# Max2_FP_v2.net
KiCad netlist of a schematic drawn in EAGLE
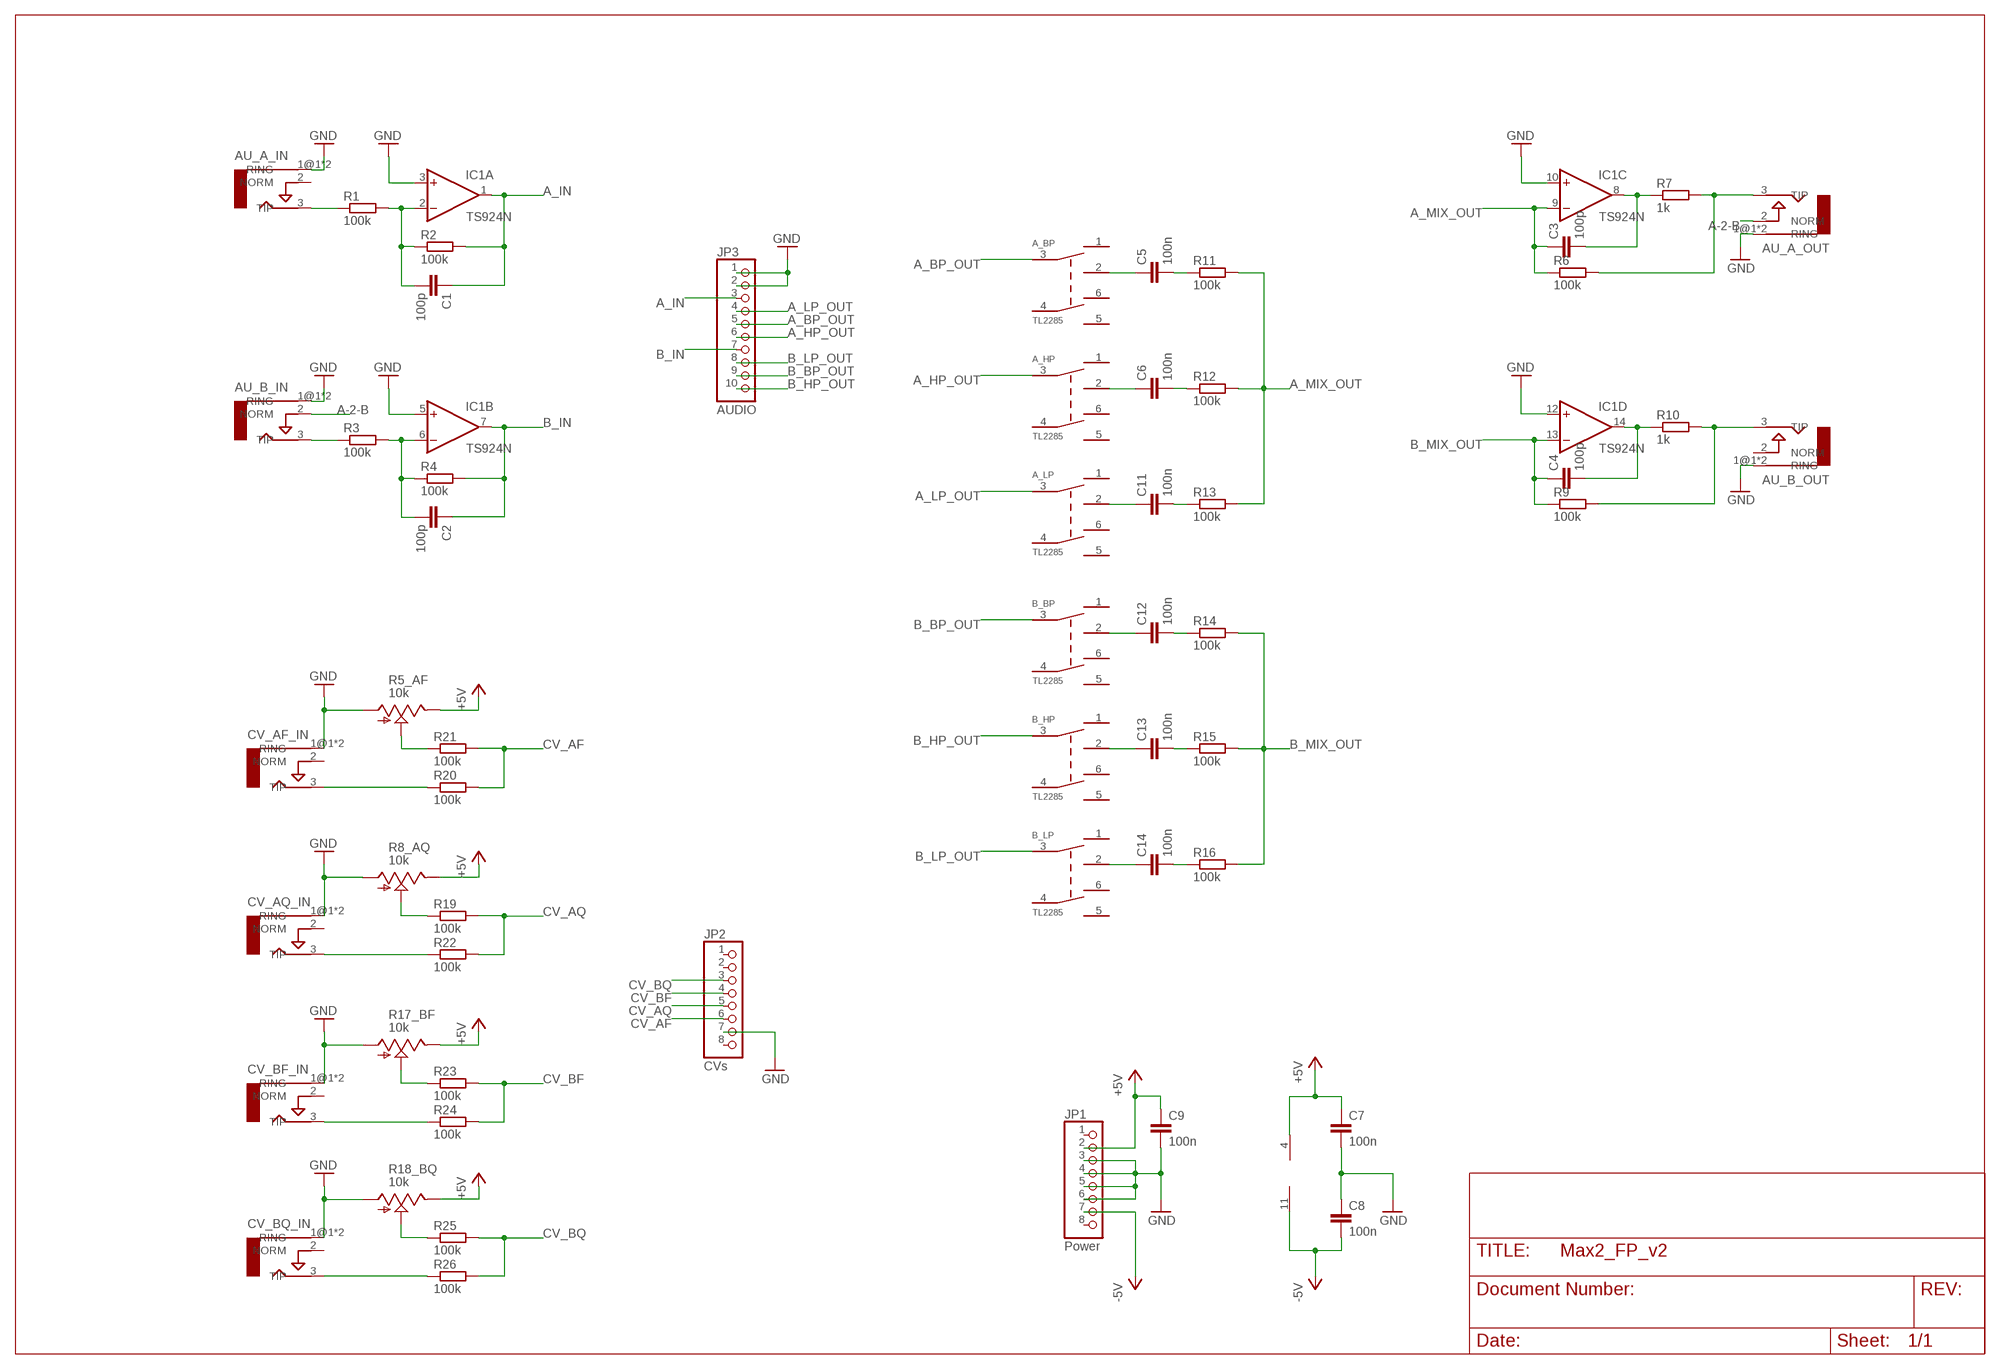
[diagram p0: schematic, sheet 1]

(export (version "E")
  (design (tool "Eeschema 10.0.6"))
  (components
    (comp (ref "AU_A_IN")
      (value "AUDIO-JACKERTHENVAR")
      (footprint "eagle-import:ERTHENVAR-JACK")
      (libsource (lib "eagle-import") (part "AUDIO-JACKERTHENVAR"))
    )
    (comp (ref "AU_A_OUT")
      (value "AUDIO-JACKERTHENVAR")
      (footprint "eagle-import:ERTHENVAR-JACK")
      (libsource (lib "eagle-import") (part "AUDIO-JACKERTHENVAR"))
    )
    (comp (ref "AU_B_IN")
      (value "AUDIO-JACKERTHENVAR")
      (footprint "eagle-import:ERTHENVAR-JACK")
      (libsource (lib "eagle-import") (part "AUDIO-JACKERTHENVAR"))
    )
    (comp (ref "AU_B_OUT")
      (value "AUDIO-JACKERTHENVAR")
      (footprint "eagle-import:ERTHENVAR-JACK")
      (libsource (lib "eagle-import") (part "AUDIO-JACKERTHENVAR"))
    )
    (comp (ref "A_BP")
      (value "TL2285")
      (footprint "eagle-import:TL2285_PCB")
      (libsource (lib "eagle-import") (part "TL2285"))
    )
    (comp (ref "A_HP")
      (value "TL2285")
      (footprint "eagle-import:TL2285_PCB")
      (libsource (lib "eagle-import") (part "TL2285"))
    )
    (comp (ref "A_LP")
      (value "TL2285")
      (footprint "eagle-import:TL2285_PCB")
      (libsource (lib "eagle-import") (part "TL2285"))
    )
    (comp (ref "B_BP")
      (value "TL2285")
      (footprint "eagle-import:TL2285_PCB")
      (libsource (lib "eagle-import") (part "TL2285"))
    )
    (comp (ref "B_HP")
      (value "TL2285")
      (footprint "eagle-import:TL2285_PCB")
      (libsource (lib "eagle-import") (part "TL2285"))
    )
    (comp (ref "B_LP")
      (value "TL2285")
      (footprint "eagle-import:TL2285_PCB")
      (libsource (lib "eagle-import") (part "TL2285"))
    )
    (comp (ref "C1")
      (value "100p")
      (footprint "eagle-import:C025-025X050")
      (libsource (lib "eagle-import") (part "C-EU025-025X050"))
    )
    (comp (ref "C2")
      (value "100p")
      (footprint "eagle-import:C025-025X050")
      (libsource (lib "eagle-import") (part "C-EU025-025X050"))
    )
    (comp (ref "C3")
      (value "100p")
      (footprint "eagle-import:C025-025X050")
      (libsource (lib "eagle-import") (part "C-EU025-025X050"))
    )
    (comp (ref "C4")
      (value "100p")
      (footprint "eagle-import:C025-025X050")
      (libsource (lib "eagle-import") (part "C-EU025-025X050"))
    )
    (comp (ref "C5")
      (value "100n")
      (footprint "eagle-import:C050-025X075")
      (libsource (lib "eagle-import") (part "C-EU050-025X075"))
    )
    (comp (ref "C6")
      (value "100n")
      (footprint "eagle-import:C050-025X075")
      (libsource (lib "eagle-import") (part "C-EU050-025X075"))
    )
    (comp (ref "C7")
      (value "100n")
      (footprint "eagle-import:C025-025X050")
      (libsource (lib "eagle-import") (part "C-EU025-025X050"))
    )
    (comp (ref "C8")
      (value "100n")
      (footprint "eagle-import:C025-025X050")
      (libsource (lib "eagle-import") (part "C-EU025-025X050"))
    )
    (comp (ref "C9")
      (value "100n")
      (footprint "eagle-import:C025-025X050")
      (libsource (lib "eagle-import") (part "C-EU025-025X050"))
    )
    (comp (ref "C11")
      (value "100n")
      (footprint "eagle-import:C050-025X075")
      (libsource (lib "eagle-import") (part "C-EU050-025X075"))
    )
    (comp (ref "C12")
      (value "100n")
      (footprint "eagle-import:C050-025X075")
      (libsource (lib "eagle-import") (part "C-EU050-025X075"))
    )
    (comp (ref "C13")
      (value "100n")
      (footprint "eagle-import:C050-025X075")
      (libsource (lib "eagle-import") (part "C-EU050-025X075"))
    )
    (comp (ref "C14")
      (value "100n")
      (footprint "eagle-import:C050-025X075")
      (libsource (lib "eagle-import") (part "C-EU050-025X075"))
    )
    (comp (ref "CV_AF_IN")
      (value "AUDIO-JACKERTHENVAR")
      (footprint "eagle-import:ERTHENVAR-JACK")
      (libsource (lib "eagle-import") (part "AUDIO-JACKERTHENVAR"))
    )
    (comp (ref "CV_AQ_IN")
      (value "AUDIO-JACKERTHENVAR")
      (footprint "eagle-import:ERTHENVAR-JACK")
      (libsource (lib "eagle-import") (part "AUDIO-JACKERTHENVAR"))
    )
    (comp (ref "CV_BF_IN")
      (value "AUDIO-JACKERTHENVAR")
      (footprint "eagle-import:ERTHENVAR-JACK")
      (libsource (lib "eagle-import") (part "AUDIO-JACKERTHENVAR"))
    )
    (comp (ref "CV_BQ_IN")
      (value "AUDIO-JACKERTHENVAR")
      (footprint "eagle-import:ERTHENVAR-JACK")
      (libsource (lib "eagle-import") (part "AUDIO-JACKERTHENVAR"))
    )
    (comp (ref "IC1")
      (value "TS924N")
      (footprint "eagle-import:DIL14")
      (libsource (lib "eagle-import") (part "TS924N"))
    )
    (comp (ref "JP1")
      (value "Power")
      (footprint "eagle-import:1X08")
      (libsource (lib "eagle-import") (part "PINHD-1X8"))
    )
    (comp (ref "JP2")
      (value "CVs")
      (footprint "eagle-import:1X08")
      (libsource (lib "eagle-import") (part "PINHD-1X8"))
    )
    (comp (ref "JP3")
      (value "AUDIO")
      (footprint "eagle-import:1X10")
      (libsource (lib "eagle-import") (part "PINHD-1X10"))
    )
    (comp (ref "R1")
      (value "100k")
      (footprint "eagle-import:0207_2V")
      (libsource (lib "eagle-import") (part "R-EU_0207/2V"))
    )
    (comp (ref "R2")
      (value "100k")
      (footprint "eagle-import:0207_2V")
      (libsource (lib "eagle-import") (part "R-EU_0207/2V"))
    )
    (comp (ref "R3")
      (value "100k")
      (footprint "eagle-import:0207_2V")
      (libsource (lib "eagle-import") (part "R-EU_0207/2V"))
    )
    (comp (ref "R4")
      (value "100k")
      (footprint "eagle-import:0207_2V")
      (libsource (lib "eagle-import") (part "R-EU_0207/2V"))
    )
    (comp (ref "R5_AF")
      (value "10k")
      (footprint "eagle-import:ALPS_POT_VERTICAL")
      (libsource (lib "eagle-import") (part "POT_USVERTICAL"))
    )
    (comp (ref "R6")
      (value "100k")
      (footprint "eagle-import:0207_2V")
      (libsource (lib "eagle-import") (part "R-EU_0207/2V"))
    )
    (comp (ref "R7")
      (value "1k")
      (footprint "eagle-import:0207_2V")
      (libsource (lib "eagle-import") (part "R-EU_0207/2V"))
    )
    (comp (ref "R8_AQ")
      (value "10k")
      (footprint "eagle-import:ALPS_POT_VERTICAL")
      (libsource (lib "eagle-import") (part "POT_USVERTICAL"))
    )
    (comp (ref "R9")
      (value "100k")
      (footprint "eagle-import:0207_2V")
      (libsource (lib "eagle-import") (part "R-EU_0207/2V"))
    )
    (comp (ref "R10")
      (value "1k")
      (footprint "eagle-import:0207_2V")
      (libsource (lib "eagle-import") (part "R-EU_0207/2V"))
    )
    (comp (ref "R11")
      (value "100k")
      (footprint "eagle-import:0207_2V")
      (libsource (lib "eagle-import") (part "R-EU_0207/2V"))
    )
    (comp (ref "R12")
      (value "100k")
      (footprint "eagle-import:0207_2V")
      (libsource (lib "eagle-import") (part "R-EU_0207/2V"))
    )
    (comp (ref "R13")
      (value "100k")
      (footprint "eagle-import:0207_2V")
      (libsource (lib "eagle-import") (part "R-EU_0207/2V"))
    )
    (comp (ref "R14")
      (value "100k")
      (footprint "eagle-import:0207_2V")
      (libsource (lib "eagle-import") (part "R-EU_0207/2V"))
    )
    (comp (ref "R15")
      (value "100k")
      (footprint "eagle-import:0207_2V")
      (libsource (lib "eagle-import") (part "R-EU_0207/2V"))
    )
    (comp (ref "R16")
      (value "100k")
      (footprint "eagle-import:0207_2V")
      (libsource (lib "eagle-import") (part "R-EU_0207/2V"))
    )
    (comp (ref "R17_BF")
      (value "10k")
      (footprint "eagle-import:ALPS_POT_VERTICAL")
      (libsource (lib "eagle-import") (part "POT_USVERTICAL"))
    )
    (comp (ref "R18_BQ")
      (value "10k")
      (footprint "eagle-import:ALPS_POT_VERTICAL")
      (libsource (lib "eagle-import") (part "POT_USVERTICAL"))
    )
    (comp (ref "R19")
      (value "100k")
      (footprint "eagle-import:0207_2V")
      (libsource (lib "eagle-import") (part "R-EU_0207/2V"))
    )
    (comp (ref "R20")
      (value "100k")
      (footprint "eagle-import:0207_2V")
      (libsource (lib "eagle-import") (part "R-EU_0207/2V"))
    )
    (comp (ref "R21")
      (value "100k")
      (footprint "eagle-import:0207_2V")
      (libsource (lib "eagle-import") (part "R-EU_0207/2V"))
    )
    (comp (ref "R22")
      (value "100k")
      (footprint "eagle-import:0207_2V")
      (libsource (lib "eagle-import") (part "R-EU_0207/2V"))
    )
    (comp (ref "R23")
      (value "100k")
      (footprint "eagle-import:0207_2V")
      (libsource (lib "eagle-import") (part "R-EU_0207/2V"))
    )
    (comp (ref "R24")
      (value "100k")
      (footprint "eagle-import:0207_2V")
      (libsource (lib "eagle-import") (part "R-EU_0207/2V"))
    )
    (comp (ref "R25")
      (value "100k")
      (footprint "eagle-import:0207_2V")
      (libsource (lib "eagle-import") (part "R-EU_0207/2V"))
    )
    (comp (ref "R26")
      (value "100k")
      (footprint "eagle-import:0207_2V")
      (libsource (lib "eagle-import") (part "R-EU_0207/2V"))
    )
  )
  (nets
    (net (code "1") (name "+5V") (class "Default")
      (node (ref "C7") (pin "1") (pinfunction "1_1") (pintype "passive"))
      (node (ref "C9") (pin "1") (pinfunction "1_1") (pintype "passive"))
      (node (ref "IC1") (pin "4") (pinfunction "V+_4") (pintype "power_in"))
      (node (ref "JP1") (pin "2") (pinfunction "2_2") (pintype "passive"))
      (node (ref "R17_BF") (pin "P$1") (pinfunction "E_P$1") (pintype "passive"))
      (node (ref "R18_BQ") (pin "P$1") (pinfunction "E_P$1") (pintype "passive"))
      (node (ref "R5_AF") (pin "P$1") (pinfunction "E_P$1") (pintype "passive"))
      (node (ref "R8_AQ") (pin "P$1") (pinfunction "E_P$1") (pintype "passive"))
    )
    (net (code "2") (name "-5V") (class "Default")
      (node (ref "C8") (pin "2") (pinfunction "2_2") (pintype "passive"))
      (node (ref "IC1") (pin "11") (pinfunction "V-_11") (pintype "power_in"))
      (node (ref "JP1") (pin "7") (pinfunction "7_7") (pintype "passive"))
    )
    (net (code "3") (name "/A-2-B") (class "Default")
      (node (ref "AU_A_OUT") (pin "2") (pinfunction "NORM_2") (pintype "bidirectional"))
      (node (ref "AU_B_IN") (pin "2") (pinfunction "NORM_2") (pintype "bidirectional"))
    )
    (net (code "4") (name "/A_BP_OUT") (class "Default")
      (node (ref "A_BP") (pin "3") (pinfunction "P3_3") (pintype "bidirectional"))
      (node (ref "JP3") (pin "5") (pinfunction "5_5") (pintype "passive"))
    )
    (net (code "5") (name "/A_HP_OUT") (class "Default")
      (node (ref "A_HP") (pin "3") (pinfunction "P3_3") (pintype "bidirectional"))
      (node (ref "JP3") (pin "6") (pinfunction "6_6") (pintype "passive"))
    )
    (net (code "6") (name "/A_IN") (class "Default")
      (node (ref "C1") (pin "1") (pinfunction "1_1") (pintype "passive"))
      (node (ref "IC1") (pin "1") (pinfunction "OUT_1") (pintype "output"))
      (node (ref "JP3") (pin "3") (pinfunction "3_3") (pintype "passive"))
      (node (ref "R2") (pin "2") (pinfunction "2_2") (pintype "passive"))
    )
    (net (code "7") (name "/A_LP_OUT") (class "Default")
      (node (ref "A_LP") (pin "3") (pinfunction "P3_3") (pintype "bidirectional"))
      (node (ref "JP3") (pin "4") (pinfunction "4_4") (pintype "passive"))
    )
    (net (code "8") (name "/A_MIX_OUT") (class "Default")
      (node (ref "C3") (pin "1") (pinfunction "1_1") (pintype "passive"))
      (node (ref "IC1") (pin "9") (pinfunction "-IN_9") (pintype "input"))
      (node (ref "R11") (pin "2") (pinfunction "2_2") (pintype "passive"))
      (node (ref "R12") (pin "2") (pinfunction "2_2") (pintype "passive"))
      (node (ref "R13") (pin "2") (pinfunction "2_2") (pintype "passive"))
      (node (ref "R6") (pin "1") (pinfunction "1_1") (pintype "passive"))
    )
    (net (code "9") (name "/B_BP_OUT") (class "Default")
      (node (ref "B_BP") (pin "3") (pinfunction "P3_3") (pintype "bidirectional"))
      (node (ref "JP3") (pin "9") (pinfunction "9_9") (pintype "passive"))
    )
    (net (code "10") (name "/B_HP_OUT") (class "Default")
      (node (ref "B_HP") (pin "3") (pinfunction "P3_3") (pintype "bidirectional"))
      (node (ref "JP3") (pin "10") (pinfunction "10_10") (pintype "passive"))
    )
    (net (code "11") (name "/B_IN") (class "Default")
      (node (ref "C2") (pin "1") (pinfunction "1_1") (pintype "passive"))
      (node (ref "IC1") (pin "7") (pinfunction "OUT_7") (pintype "output"))
      (node (ref "JP3") (pin "7") (pinfunction "7_7") (pintype "passive"))
      (node (ref "R4") (pin "2") (pinfunction "2_2") (pintype "passive"))
    )
    (net (code "12") (name "/B_LP_OUT") (class "Default")
      (node (ref "B_LP") (pin "3") (pinfunction "P3_3") (pintype "bidirectional"))
      (node (ref "JP3") (pin "8") (pinfunction "8_8") (pintype "passive"))
    )
    (net (code "13") (name "/B_MIX_OUT") (class "Default")
      (node (ref "C4") (pin "1") (pinfunction "1_1") (pintype "passive"))
      (node (ref "IC1") (pin "13") (pinfunction "-IN_13") (pintype "input"))
      (node (ref "R14") (pin "2") (pinfunction "2_2") (pintype "passive"))
      (node (ref "R15") (pin "2") (pinfunction "2_2") (pintype "passive"))
      (node (ref "R16") (pin "2") (pinfunction "2_2") (pintype "passive"))
      (node (ref "R9") (pin "1") (pinfunction "1_1") (pintype "passive"))
    )
    (net (code "14") (name "/CV_AF") (class "Default")
      (node (ref "JP2") (pin "6") (pinfunction "6_6") (pintype "passive"))
      (node (ref "R20") (pin "2") (pinfunction "2_2") (pintype "passive"))
      (node (ref "R21") (pin "2") (pinfunction "2_2") (pintype "passive"))
    )
    (net (code "15") (name "/CV_AQ") (class "Default")
      (node (ref "JP2") (pin "5") (pinfunction "5_5") (pintype "passive"))
      (node (ref "R19") (pin "2") (pinfunction "2_2") (pintype "passive"))
      (node (ref "R22") (pin "2") (pinfunction "2_2") (pintype "passive"))
    )
    (net (code "16") (name "/CV_BF") (class "Default")
      (node (ref "JP2") (pin "4") (pinfunction "4_4") (pintype "passive"))
      (node (ref "R23") (pin "2") (pinfunction "2_2") (pintype "passive"))
      (node (ref "R24") (pin "2") (pinfunction "2_2") (pintype "passive"))
    )
    (net (code "17") (name "/CV_BQ") (class "Default")
      (node (ref "JP2") (pin "3") (pinfunction "3_3") (pintype "passive"))
      (node (ref "R25") (pin "2") (pinfunction "2_2") (pintype "passive"))
      (node (ref "R26") (pin "2") (pinfunction "2_2") (pintype "passive"))
    )
    (net (code "18") (name "GND") (class "Default")
      (node (ref "AU_A_IN") (pin "1@1") (pinfunction "RING_1@1") (pintype "bidirectional"))
      (node (ref "AU_A_IN") (pin "1@2") (pinfunction "RING_1@2") (pintype "bidirectional"))
      (node (ref "AU_A_OUT") (pin "1@1") (pinfunction "RING_1@1") (pintype "bidirectional"))
      (node (ref "AU_A_OUT") (pin "1@2") (pinfunction "RING_1@2") (pintype "bidirectional"))
      (node (ref "AU_B_IN") (pin "1@1") (pinfunction "RING_1@1") (pintype "bidirectional"))
      (node (ref "AU_B_IN") (pin "1@2") (pinfunction "RING_1@2") (pintype "bidirectional"))
      (node (ref "AU_B_OUT") (pin "1@1") (pinfunction "RING_1@1") (pintype "bidirectional"))
      (node (ref "AU_B_OUT") (pin "1@2") (pinfunction "RING_1@2") (pintype "bidirectional"))
      (node (ref "C7") (pin "2") (pinfunction "2_2") (pintype "passive"))
      (node (ref "C8") (pin "1") (pinfunction "1_1") (pintype "passive"))
      (node (ref "C9") (pin "2") (pinfunction "2_2") (pintype "passive"))
      (node (ref "CV_AF_IN") (pin "1@1") (pinfunction "RING_1@1") (pintype "bidirectional"))
      (node (ref "CV_AF_IN") (pin "1@2") (pinfunction "RING_1@2") (pintype "bidirectional"))
      (node (ref "CV_AQ_IN") (pin "1@1") (pinfunction "RING_1@1") (pintype "bidirectional"))
      (node (ref "CV_AQ_IN") (pin "1@2") (pinfunction "RING_1@2") (pintype "bidirectional"))
      (node (ref "CV_BF_IN") (pin "1@1") (pinfunction "RING_1@1") (pintype "bidirectional"))
      (node (ref "CV_BF_IN") (pin "1@2") (pinfunction "RING_1@2") (pintype "bidirectional"))
      (node (ref "CV_BQ_IN") (pin "1@1") (pinfunction "RING_1@1") (pintype "bidirectional"))
      (node (ref "CV_BQ_IN") (pin "1@2") (pinfunction "RING_1@2") (pintype "bidirectional"))
      (node (ref "IC1") (pin "10") (pinfunction "+IN_10") (pintype "input"))
      (node (ref "IC1") (pin "12") (pinfunction "+IN_12") (pintype "input"))
      (node (ref "IC1") (pin "3") (pinfunction "+IN_3") (pintype "input"))
      (node (ref "IC1") (pin "5") (pinfunction "+IN_5") (pintype "input"))
      (node (ref "JP1") (pin "3") (pinfunction "3_3") (pintype "passive"))
      (node (ref "JP1") (pin "4") (pinfunction "4_4") (pintype "passive"))
      (node (ref "JP1") (pin "5") (pinfunction "5_5") (pintype "passive"))
      (node (ref "JP1") (pin "6") (pinfunction "6_6") (pintype "passive"))
      (node (ref "JP2") (pin "7") (pinfunction "7_7") (pintype "passive"))
      (node (ref "JP3") (pin "1") (pinfunction "1_1") (pintype "passive"))
      (node (ref "JP3") (pin "2") (pinfunction "2_2") (pintype "passive"))
      (node (ref "R17_BF") (pin "P$3") (pinfunction "A_P$3") (pintype "passive"))
      (node (ref "R18_BQ") (pin "P$3") (pinfunction "A_P$3") (pintype "passive"))
      (node (ref "R5_AF") (pin "P$3") (pinfunction "A_P$3") (pintype "passive"))
      (node (ref "R8_AQ") (pin "P$3") (pinfunction "A_P$3") (pintype "passive"))
    )
    (net (code "19") (name "Net-(AU_A_IN-TIP)") (class "Default")
      (node (ref "AU_A_IN") (pin "3") (pinfunction "TIP_3") (pintype "bidirectional"))
      (node (ref "R1") (pin "1") (pinfunction "1_1") (pintype "passive"))
    )
    (net (code "20") (name "Net-(AU_A_OUT-TIP)") (class "Default")
      (node (ref "AU_A_OUT") (pin "3") (pinfunction "TIP_3") (pintype "bidirectional"))
      (node (ref "R6") (pin "2") (pinfunction "2_2") (pintype "passive"))
      (node (ref "R7") (pin "2") (pinfunction "2_2") (pintype "passive"))
    )
    (net (code "21") (name "Net-(AU_B_IN-TIP)") (class "Default")
      (node (ref "AU_B_IN") (pin "3") (pinfunction "TIP_3") (pintype "bidirectional"))
      (node (ref "R3") (pin "1") (pinfunction "1_1") (pintype "passive"))
    )
    (net (code "22") (name "Net-(AU_B_OUT-TIP)") (class "Default")
      (node (ref "AU_B_OUT") (pin "3") (pinfunction "TIP_3") (pintype "bidirectional"))
      (node (ref "R10") (pin "2") (pinfunction "2_2") (pintype "passive"))
      (node (ref "R9") (pin "2") (pinfunction "2_2") (pintype "passive"))
    )
    (net (code "23") (name "Net-(A_BP-P2)") (class "Default")
      (node (ref "A_BP") (pin "2") (pinfunction "P2_2") (pintype "bidirectional"))
      (node (ref "C5") (pin "1") (pinfunction "1_1") (pintype "passive"))
    )
    (net (code "24") (name "Net-(A_HP-P2)") (class "Default")
      (node (ref "A_HP") (pin "2") (pinfunction "P2_2") (pintype "bidirectional"))
      (node (ref "C6") (pin "1") (pinfunction "1_1") (pintype "passive"))
    )
    (net (code "25") (name "Net-(A_LP-P2)") (class "Default")
      (node (ref "A_LP") (pin "2") (pinfunction "P2_2") (pintype "bidirectional"))
      (node (ref "C11") (pin "1") (pinfunction "1_1") (pintype "passive"))
    )
    (net (code "26") (name "Net-(B_BP-P2)") (class "Default")
      (node (ref "B_BP") (pin "2") (pinfunction "P2_2") (pintype "bidirectional"))
      (node (ref "C12") (pin "1") (pinfunction "1_1") (pintype "passive"))
    )
    (net (code "27") (name "Net-(B_HP-P2)") (class "Default")
      (node (ref "B_HP") (pin "2") (pinfunction "P2_2") (pintype "bidirectional"))
      (node (ref "C13") (pin "1") (pinfunction "1_1") (pintype "passive"))
    )
    (net (code "28") (name "Net-(B_LP-P2)") (class "Default")
      (node (ref "B_LP") (pin "2") (pinfunction "P2_2") (pintype "bidirectional"))
      (node (ref "C14") (pin "1") (pinfunction "1_1") (pintype "passive"))
    )
    (net (code "29") (name "Net-(C5-Pad2)") (class "Default")
      (node (ref "C5") (pin "2") (pinfunction "2_2") (pintype "passive"))
      (node (ref "R11") (pin "1") (pinfunction "1_1") (pintype "passive"))
    )
    (net (code "30") (name "Net-(C6-Pad2)") (class "Default")
      (node (ref "C6") (pin "2") (pinfunction "2_2") (pintype "passive"))
      (node (ref "R12") (pin "1") (pinfunction "1_1") (pintype "passive"))
    )
    (net (code "31") (name "Net-(C11-Pad2)") (class "Default")
      (node (ref "C11") (pin "2") (pinfunction "2_2") (pintype "passive"))
      (node (ref "R13") (pin "1") (pinfunction "1_1") (pintype "passive"))
    )
    (net (code "32") (name "Net-(C12-Pad2)") (class "Default")
      (node (ref "C12") (pin "2") (pinfunction "2_2") (pintype "passive"))
      (node (ref "R14") (pin "1") (pinfunction "1_1") (pintype "passive"))
    )
    (net (code "33") (name "Net-(C13-Pad2)") (class "Default")
      (node (ref "C13") (pin "2") (pinfunction "2_2") (pintype "passive"))
      (node (ref "R15") (pin "1") (pinfunction "1_1") (pintype "passive"))
    )
    (net (code "34") (name "Net-(C14-Pad2)") (class "Default")
      (node (ref "C14") (pin "2") (pinfunction "2_2") (pintype "passive"))
      (node (ref "R16") (pin "1") (pinfunction "1_1") (pintype "passive"))
    )
    (net (code "35") (name "Net-(CV_AF_IN-TIP)") (class "Default")
      (node (ref "CV_AF_IN") (pin "3") (pinfunction "TIP_3") (pintype "bidirectional"))
      (node (ref "R20") (pin "1") (pinfunction "1_1") (pintype "passive"))
    )
    (net (code "36") (name "Net-(CV_AQ_IN-TIP)") (class "Default")
      (node (ref "CV_AQ_IN") (pin "3") (pinfunction "TIP_3") (pintype "bidirectional"))
      (node (ref "R22") (pin "1") (pinfunction "1_1") (pintype "passive"))
    )
    (net (code "37") (name "Net-(CV_BF_IN-TIP)") (class "Default")
      (node (ref "CV_BF_IN") (pin "3") (pinfunction "TIP_3") (pintype "bidirectional"))
      (node (ref "R24") (pin "1") (pinfunction "1_1") (pintype "passive"))
    )
    (net (code "38") (name "Net-(CV_BQ_IN-TIP)") (class "Default")
      (node (ref "CV_BQ_IN") (pin "3") (pinfunction "TIP_3") (pintype "bidirectional"))
      (node (ref "R26") (pin "1") (pinfunction "1_1") (pintype "passive"))
    )
    (net (code "39") (name "Net-(IC1A--IN)") (class "Default")
      (node (ref "C1") (pin "2") (pinfunction "2_2") (pintype "passive"))
      (node (ref "IC1") (pin "2") (pinfunction "-IN_2") (pintype "input"))
      (node (ref "R1") (pin "2") (pinfunction "2_2") (pintype "passive"))
      (node (ref "R2") (pin "1") (pinfunction "1_1") (pintype "passive"))
    )
    (net (code "40") (name "Net-(IC1B--IN)") (class "Default")
      (node (ref "C2") (pin "2") (pinfunction "2_2") (pintype "passive"))
      (node (ref "IC1") (pin "6") (pinfunction "-IN_6") (pintype "input"))
      (node (ref "R3") (pin "2") (pinfunction "2_2") (pintype "passive"))
      (node (ref "R4") (pin "1") (pinfunction "1_1") (pintype "passive"))
    )
    (net (code "41") (name "Net-(IC1C-OUT)") (class "Default")
      (node (ref "C3") (pin "2") (pinfunction "2_2") (pintype "passive"))
      (node (ref "IC1") (pin "8") (pinfunction "OUT_8") (pintype "output"))
      (node (ref "R7") (pin "1") (pinfunction "1_1") (pintype "passive"))
    )
    (net (code "42") (name "Net-(IC1D-OUT)") (class "Default")
      (node (ref "C4") (pin "2") (pinfunction "2_2") (pintype "passive"))
      (node (ref "IC1") (pin "14") (pinfunction "OUT_14") (pintype "output"))
      (node (ref "R10") (pin "1") (pinfunction "1_1") (pintype "passive"))
    )
    (net (code "43") (name "Net-(R5_AF-S)") (class "Default")
      (node (ref "R21") (pin "1") (pinfunction "1_1") (pintype "passive"))
      (node (ref "R5_AF") (pin "P$2") (pinfunction "S_P$2") (pintype "passive"))
    )
    (net (code "44") (name "Net-(R8_AQ-S)") (class "Default")
      (node (ref "R19") (pin "1") (pinfunction "1_1") (pintype "passive"))
      (node (ref "R8_AQ") (pin "P$2") (pinfunction "S_P$2") (pintype "passive"))
    )
    (net (code "45") (name "Net-(R17_BF-S)") (class "Default")
      (node (ref "R17_BF") (pin "P$2") (pinfunction "S_P$2") (pintype "passive"))
      (node (ref "R23") (pin "1") (pinfunction "1_1") (pintype "passive"))
    )
    (net (code "46") (name "Net-(R18_BQ-S)") (class "Default")
      (node (ref "R18_BQ") (pin "P$2") (pinfunction "S_P$2") (pintype "passive"))
      (node (ref "R25") (pin "1") (pinfunction "1_1") (pintype "passive"))
    )
    (net (code "47") (name "unconnected-(AU_A_IN-NORM-Pad2)") (class "Default")
      (node (ref "AU_A_IN") (pin "2") (pinfunction "NORM_2") (pintype "bidirectional"))
    )
    (net (code "48") (name "unconnected-(AU_B_OUT-NORM-Pad2)") (class "Default")
      (node (ref "AU_B_OUT") (pin "2") (pinfunction "NORM_2") (pintype "bidirectional"))
    )
    (net (code "49") (name "unconnected-(A_BP-P1-Pad1)") (class "Default")
      (node (ref "A_BP") (pin "1") (pinfunction "P1_1") (pintype "bidirectional"))
    )
    (net (code "50") (name "unconnected-(A_BP-P4-Pad4)") (class "Default")
      (node (ref "A_BP") (pin "4") (pinfunction "P4_4") (pintype "bidirectional"))
    )
    (net (code "51") (name "unconnected-(A_BP-P5-Pad5)") (class "Default")
      (node (ref "A_BP") (pin "5") (pinfunction "P5_5") (pintype "bidirectional"))
    )
    (net (code "52") (name "unconnected-(A_BP-P6-Pad6)") (class "Default")
      (node (ref "A_BP") (pin "6") (pinfunction "P6_6") (pintype "bidirectional"))
    )
    (net (code "53") (name "unconnected-(A_HP-P1-Pad1)") (class "Default")
      (node (ref "A_HP") (pin "1") (pinfunction "P1_1") (pintype "bidirectional"))
    )
    (net (code "54") (name "unconnected-(A_HP-P4-Pad4)") (class "Default")
      (node (ref "A_HP") (pin "4") (pinfunction "P4_4") (pintype "bidirectional"))
    )
    (net (code "55") (name "unconnected-(A_HP-P5-Pad5)") (class "Default")
      (node (ref "A_HP") (pin "5") (pinfunction "P5_5") (pintype "bidirectional"))
    )
    (net (code "56") (name "unconnected-(A_HP-P6-Pad6)") (class "Default")
      (node (ref "A_HP") (pin "6") (pinfunction "P6_6") (pintype "bidirectional"))
    )
    (net (code "57") (name "unconnected-(A_LP-P1-Pad1)") (class "Default")
      (node (ref "A_LP") (pin "1") (pinfunction "P1_1") (pintype "bidirectional"))
    )
    (net (code "58") (name "unconnected-(A_LP-P4-Pad4)") (class "Default")
      (node (ref "A_LP") (pin "4") (pinfunction "P4_4") (pintype "bidirectional"))
    )
    (net (code "59") (name "unconnected-(A_LP-P5-Pad5)") (class "Default")
      (node (ref "A_LP") (pin "5") (pinfunction "P5_5") (pintype "bidirectional"))
    )
    (net (code "60") (name "unconnected-(A_LP-P6-Pad6)") (class "Default")
      (node (ref "A_LP") (pin "6") (pinfunction "P6_6") (pintype "bidirectional"))
    )
    (net (code "61") (name "unconnected-(B_BP-P1-Pad1)") (class "Default")
      (node (ref "B_BP") (pin "1") (pinfunction "P1_1") (pintype "bidirectional"))
    )
    (net (code "62") (name "unconnected-(B_BP-P4-Pad4)") (class "Default")
      (node (ref "B_BP") (pin "4") (pinfunction "P4_4") (pintype "bidirectional"))
    )
    (net (code "63") (name "unconnected-(B_BP-P5-Pad5)") (class "Default")
      (node (ref "B_BP") (pin "5") (pinfunction "P5_5") (pintype "bidirectional"))
    )
    (net (code "64") (name "unconnected-(B_BP-P6-Pad6)") (class "Default")
      (node (ref "B_BP") (pin "6") (pinfunction "P6_6") (pintype "bidirectional"))
    )
    (net (code "65") (name "unconnected-(B_HP-P1-Pad1)") (class "Default")
      (node (ref "B_HP") (pin "1") (pinfunction "P1_1") (pintype "bidirectional"))
    )
    (net (code "66") (name "unconnected-(B_HP-P4-Pad4)") (class "Default")
      (node (ref "B_HP") (pin "4") (pinfunction "P4_4") (pintype "bidirectional"))
    )
    (net (code "67") (name "unconnected-(B_HP-P5-Pad5)") (class "Default")
      (node (ref "B_HP") (pin "5") (pinfunction "P5_5") (pintype "bidirectional"))
    )
    (net (code "68") (name "unconnected-(B_HP-P6-Pad6)") (class "Default")
      (node (ref "B_HP") (pin "6") (pinfunction "P6_6") (pintype "bidirectional"))
    )
    (net (code "69") (name "unconnected-(B_LP-P1-Pad1)") (class "Default")
      (node (ref "B_LP") (pin "1") (pinfunction "P1_1") (pintype "bidirectional"))
    )
    (net (code "70") (name "unconnected-(B_LP-P4-Pad4)") (class "Default")
      (node (ref "B_LP") (pin "4") (pinfunction "P4_4") (pintype "bidirectional"))
    )
    (net (code "71") (name "unconnected-(B_LP-P5-Pad5)") (class "Default")
      (node (ref "B_LP") (pin "5") (pinfunction "P5_5") (pintype "bidirectional"))
    )
    (net (code "72") (name "unconnected-(B_LP-P6-Pad6)") (class "Default")
      (node (ref "B_LP") (pin "6") (pinfunction "P6_6") (pintype "bidirectional"))
    )
    (net (code "73") (name "unconnected-(CV_AF_IN-NORM-Pad2)") (class "Default")
      (node (ref "CV_AF_IN") (pin "2") (pinfunction "NORM_2") (pintype "bidirectional"))
    )
    (net (code "74") (name "unconnected-(CV_AQ_IN-NORM-Pad2)") (class "Default")
      (node (ref "CV_AQ_IN") (pin "2") (pinfunction "NORM_2") (pintype "bidirectional"))
    )
    (net (code "75") (name "unconnected-(CV_BF_IN-NORM-Pad2)") (class "Default")
      (node (ref "CV_BF_IN") (pin "2") (pinfunction "NORM_2") (pintype "bidirectional"))
    )
    (net (code "76") (name "unconnected-(CV_BQ_IN-NORM-Pad2)") (class "Default")
      (node (ref "CV_BQ_IN") (pin "2") (pinfunction "NORM_2") (pintype "bidirectional"))
    )
    (net (code "77") (name "unconnected-(JP1-Pad1)") (class "Default")
      (node (ref "JP1") (pin "1") (pinfunction "1_1") (pintype "passive"))
    )
    (net (code "78") (name "unconnected-(JP1-Pad8)") (class "Default")
      (node (ref "JP1") (pin "8") (pinfunction "8_8") (pintype "passive"))
    )
    (net (code "79") (name "unconnected-(JP2-Pad1)") (class "Default")
      (node (ref "JP2") (pin "1") (pinfunction "1_1") (pintype "passive"))
    )
    (net (code "80") (name "unconnected-(JP2-Pad2)") (class "Default")
      (node (ref "JP2") (pin "2") (pinfunction "2_2") (pintype "passive"))
    )
    (net (code "81") (name "unconnected-(JP2-Pad8)") (class "Default")
      (node (ref "JP2") (pin "8") (pinfunction "8_8") (pintype "passive"))
    )
  )
)
